# newbrd.net
KiCad netlist of a schematic drawn in EAGLE
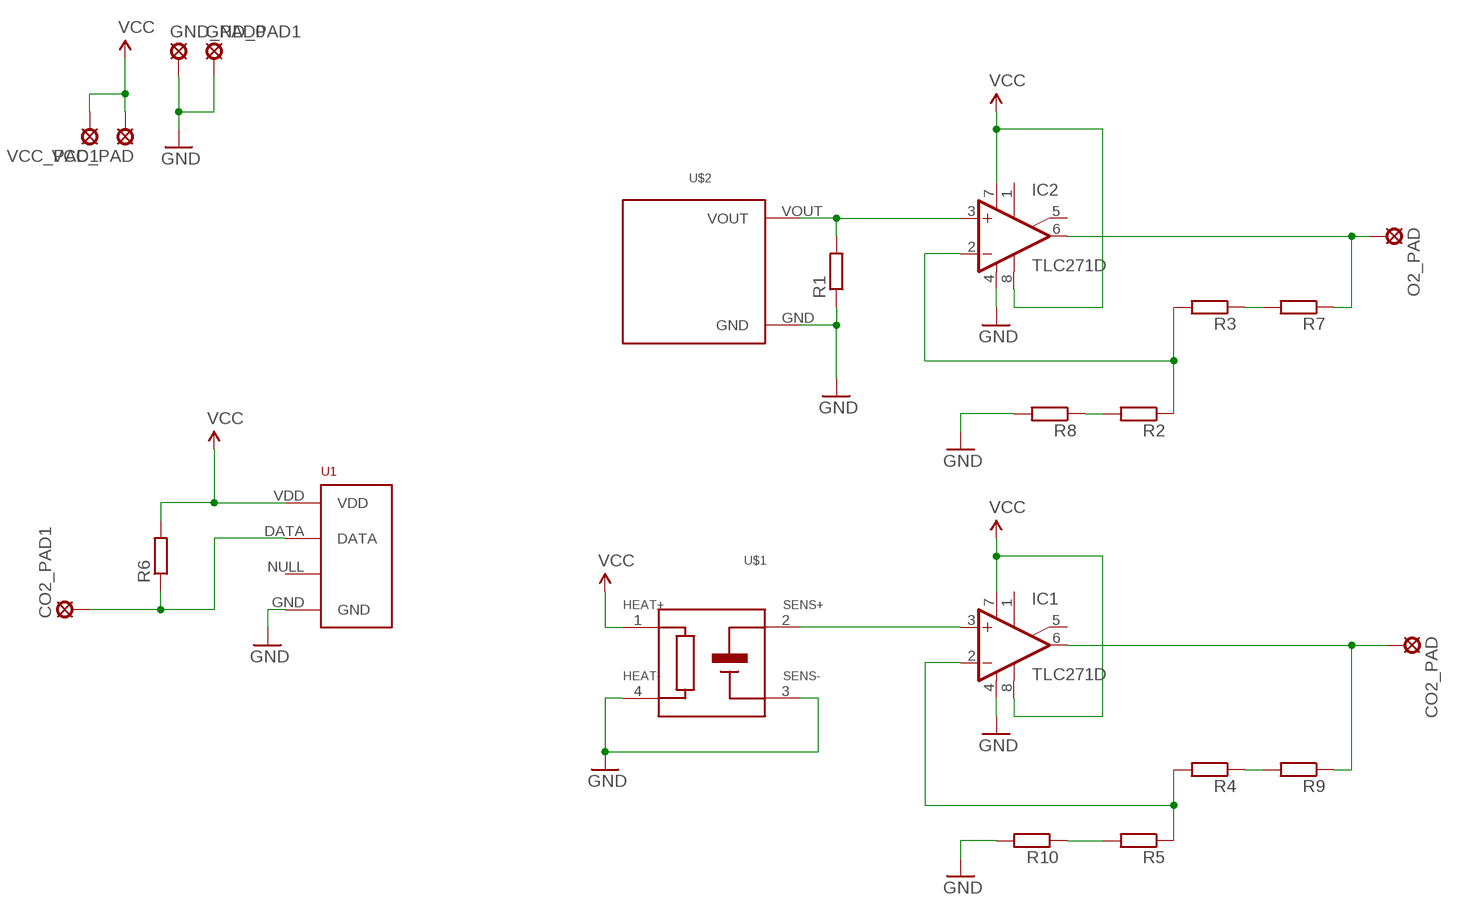
[diagram p0: schematic, sheet 1]

(export (version "E")
  (design (tool "Eeschema 10.0.6"))
  (components
    (comp (ref "CO2_PAD")
      (value "LSP10")
      (footprint "eagle-import:LSP10")
      (libsource (lib "eagle-import") (part "LSP10"))
    )
    (comp (ref "CO2_PAD1")
      (value "LSP10")
      (footprint "eagle-import:LSP10")
      (libsource (lib "eagle-import") (part "LSP10"))
    )
    (comp (ref "GND_PAD0")
      (value "LSP10")
      (footprint "eagle-import:LSP10")
      (libsource (lib "eagle-import") (part "LSP10"))
    )
    (comp (ref "GND_PAD1")
      (value "LSP10")
      (footprint "eagle-import:LSP10")
      (libsource (lib "eagle-import") (part "LSP10"))
    )
    (comp (ref "IC1")
      (value "TLC271D")
      (footprint "eagle-import:SO08")
      (libsource (lib "eagle-import") (part "TLC271D"))
    )
    (comp (ref "IC2")
      (value "TLC271D")
      (footprint "eagle-import:SO08")
      (libsource (lib "eagle-import") (part "TLC271D"))
    )
    (comp (ref "O2_PAD")
      (value "LSP10")
      (footprint "eagle-import:LSP10")
      (libsource (lib "eagle-import") (part "LSP10"))
    )
    (comp (ref "R1")
      (value "R-EU_R0805")
      (footprint "eagle-import:R0805")
      (libsource (lib "eagle-import") (part "R-EU_R0805"))
    )
    (comp (ref "R2")
      (value "R-EU_R0805")
      (footprint "eagle-import:R0805")
      (libsource (lib "eagle-import") (part "R-EU_R0805"))
    )
    (comp (ref "R3")
      (value "R-EU_R0805")
      (footprint "eagle-import:R0805")
      (libsource (lib "eagle-import") (part "R-EU_R0805"))
    )
    (comp (ref "R4")
      (value "R-EU_R0805")
      (footprint "eagle-import:R0805")
      (libsource (lib "eagle-import") (part "R-EU_R0805"))
    )
    (comp (ref "R5")
      (value "R-EU_R0805")
      (footprint "eagle-import:R0805")
      (libsource (lib "eagle-import") (part "R-EU_R0805"))
    )
    (comp (ref "R6")
      (value "R-EU_R0805")
      (footprint "eagle-import:R0805")
      (libsource (lib "eagle-import") (part "R-EU_R0805"))
    )
    (comp (ref "R7")
      (value "R-EU_R0805")
      (footprint "eagle-import:R0805")
      (libsource (lib "eagle-import") (part "R-EU_R0805"))
    )
    (comp (ref "R8")
      (value "R-EU_R0805")
      (footprint "eagle-import:R0805")
      (libsource (lib "eagle-import") (part "R-EU_R0805"))
    )
    (comp (ref "R9")
      (value "R-EU_R0805")
      (footprint "eagle-import:R0805")
      (libsource (lib "eagle-import") (part "R-EU_R0805"))
    )
    (comp (ref "R10")
      (value "R-EU_R0805")
      (footprint "eagle-import:R0805")
      (libsource (lib "eagle-import") (part "R-EU_R0805"))
    )
    (comp (ref "U$1")
      (value "TGS4161")
      (footprint "eagle-import:TGS4161")
      (libsource (lib "eagle-import") (part "TGS4161"))
    )
    (comp (ref "U$2")
      (value "O2-A2")
      (footprint "eagle-import:O2-A2")
      (libsource (lib "eagle-import") (part "O2-A2"))
    )
    (comp (ref "U1")
      (value "RHT03_DHT-22_AM2302RA")
      (footprint "eagle-import:RHT03_DHT-22_RA")
      (libsource (lib "eagle-import") (part "RHT03_DHT-22_AM2302RA"))
    )
    (comp (ref "VCC_PAD")
      (value "LSP10")
      (footprint "eagle-import:LSP10")
      (libsource (lib "eagle-import") (part "LSP10"))
    )
    (comp (ref "VCC_PAD1")
      (value "LSP10")
      (footprint "eagle-import:LSP10")
      (libsource (lib "eagle-import") (part "LSP10"))
    )
  )
  (nets
    (net (code "1") (name "GND") (class "Default")
      (node (ref "GND_PAD0") (pin "MP") (pinfunction "MP_MP") (pintype "passive"))
      (node (ref "GND_PAD1") (pin "MP") (pinfunction "MP_MP") (pintype "passive"))
      (node (ref "IC1") (pin "4") (pinfunction "V-_4") (pintype "power_in"))
      (node (ref "IC2") (pin "4") (pinfunction "V-_4") (pintype "power_in"))
      (node (ref "R1") (pin "1") (pinfunction "1_1") (pintype "passive"))
      (node (ref "R10") (pin "2") (pinfunction "2_2") (pintype "passive"))
      (node (ref "R8") (pin "2") (pinfunction "2_2") (pintype "passive"))
      (node (ref "U$1") (pin "3") (pinfunction "SENS-_3") (pintype "passive"))
      (node (ref "U$1") (pin "4") (pinfunction "HEAT-_4") (pintype "power_in"))
      (node (ref "U$2") (pin "GND") (pinfunction "GND_GND") (pintype "bidirectional"))
      (node (ref "U1") (pin "GND") (pinfunction "GND_GND") (pintype "power_in"))
    )
    (net (code "2") (name "Net-(CO2_PAD1-PadMP)") (class "Default")
      (node (ref "CO2_PAD1") (pin "MP") (pinfunction "MP_MP") (pintype "passive"))
      (node (ref "R6") (pin "1") (pinfunction "1_1") (pintype "passive"))
      (node (ref "U1") (pin "DATA") (pinfunction "DATA_DATA") (pintype "bidirectional"))
    )
    (net (code "3") (name "Net-(IC1-+IN)") (class "Default")
      (node (ref "IC1") (pin "3") (pinfunction "+IN_3") (pintype "input"))
      (node (ref "U$1") (pin "2") (pinfunction "SENS+_2") (pintype "passive"))
    )
    (net (code "4") (name "Net-(IC1--IN)") (class "Default")
      (node (ref "IC1") (pin "2") (pinfunction "-IN_2") (pintype "input"))
      (node (ref "R4") (pin "2") (pinfunction "2_2") (pintype "passive"))
      (node (ref "R5") (pin "1") (pinfunction "1_1") (pintype "passive"))
    )
    (net (code "5") (name "Net-(IC1-OUT)") (class "Default")
      (node (ref "CO2_PAD") (pin "MP") (pinfunction "MP_MP") (pintype "passive"))
      (node (ref "IC1") (pin "6") (pinfunction "OUT_6") (pintype "output"))
      (node (ref "R9") (pin "1") (pinfunction "1_1") (pintype "passive"))
    )
    (net (code "6") (name "Net-(IC2-+IN)") (class "Default")
      (node (ref "IC2") (pin "3") (pinfunction "+IN_3") (pintype "input"))
      (node (ref "R1") (pin "2") (pinfunction "2_2") (pintype "passive"))
      (node (ref "U$2") (pin "VOUT") (pinfunction "VOUT_VOUT") (pintype "bidirectional"))
    )
    (net (code "7") (name "Net-(IC2--IN)") (class "Default")
      (node (ref "IC2") (pin "2") (pinfunction "-IN_2") (pintype "input"))
      (node (ref "R2") (pin "1") (pinfunction "1_1") (pintype "passive"))
      (node (ref "R3") (pin "2") (pinfunction "2_2") (pintype "passive"))
    )
    (net (code "8") (name "Net-(IC2-OUT)") (class "Default")
      (node (ref "IC2") (pin "6") (pinfunction "OUT_6") (pintype "output"))
      (node (ref "O2_PAD") (pin "MP") (pinfunction "MP_MP") (pintype "passive"))
      (node (ref "R7") (pin "1") (pinfunction "1_1") (pintype "passive"))
    )
    (net (code "9") (name "Net-(R2-Pad2)") (class "Default")
      (node (ref "R2") (pin "2") (pinfunction "2_2") (pintype "passive"))
      (node (ref "R8") (pin "1") (pinfunction "1_1") (pintype "passive"))
    )
    (net (code "10") (name "Net-(R3-Pad1)") (class "Default")
      (node (ref "R3") (pin "1") (pinfunction "1_1") (pintype "passive"))
      (node (ref "R7") (pin "2") (pinfunction "2_2") (pintype "passive"))
    )
    (net (code "11") (name "Net-(R4-Pad1)") (class "Default")
      (node (ref "R4") (pin "1") (pinfunction "1_1") (pintype "passive"))
      (node (ref "R9") (pin "2") (pinfunction "2_2") (pintype "passive"))
    )
    (net (code "12") (name "Net-(R10-Pad1)") (class "Default")
      (node (ref "R10") (pin "1") (pinfunction "1_1") (pintype "passive"))
      (node (ref "R5") (pin "2") (pinfunction "2_2") (pintype "passive"))
    )
    (net (code "13") (name "VCC") (class "Default")
      (node (ref "IC1") (pin "7") (pinfunction "V+_7") (pintype "power_in"))
      (node (ref "IC1") (pin "8") (pinfunction "OPT_8") (pintype "passive"))
      (node (ref "IC2") (pin "7") (pinfunction "V+_7") (pintype "power_in"))
      (node (ref "IC2") (pin "8") (pinfunction "OPT_8") (pintype "passive"))
      (node (ref "R6") (pin "2") (pinfunction "2_2") (pintype "passive"))
      (node (ref "U$1") (pin "1") (pinfunction "HEAT+_1") (pintype "power_in"))
      (node (ref "U1") (pin "VDD") (pinfunction "VDD_VDD") (pintype "power_in"))
      (node (ref "VCC_PAD") (pin "MP") (pinfunction "MP_MP") (pintype "passive"))
      (node (ref "VCC_PAD1") (pin "MP") (pinfunction "MP_MP") (pintype "passive"))
    )
    (net (code "14") (name "unconnected-(IC1-ON1-Pad1)") (class "Default")
      (node (ref "IC1") (pin "1") (pinfunction "ON1_1") (pintype "passive"))
    )
    (net (code "15") (name "unconnected-(IC1-ON2-Pad5)") (class "Default")
      (node (ref "IC1") (pin "5") (pinfunction "ON2_5") (pintype "passive"))
    )
    (net (code "16") (name "unconnected-(IC2-ON1-Pad1)") (class "Default")
      (node (ref "IC2") (pin "1") (pinfunction "ON1_1") (pintype "passive"))
    )
    (net (code "17") (name "unconnected-(IC2-ON2-Pad5)") (class "Default")
      (node (ref "IC2") (pin "5") (pinfunction "ON2_5") (pintype "passive"))
    )
    (net (code "18") (name "unconnected-(U1-PadNULL)") (class "Default")
      (node (ref "U1") (pin "NULL") (pinfunction "NULL_NULL") (pintype "no_connect"))
    )
  )
)
